# 2021-02-18_HALO_Accel_Board.net
KiCad netlist of a schematic drawn in EAGLE
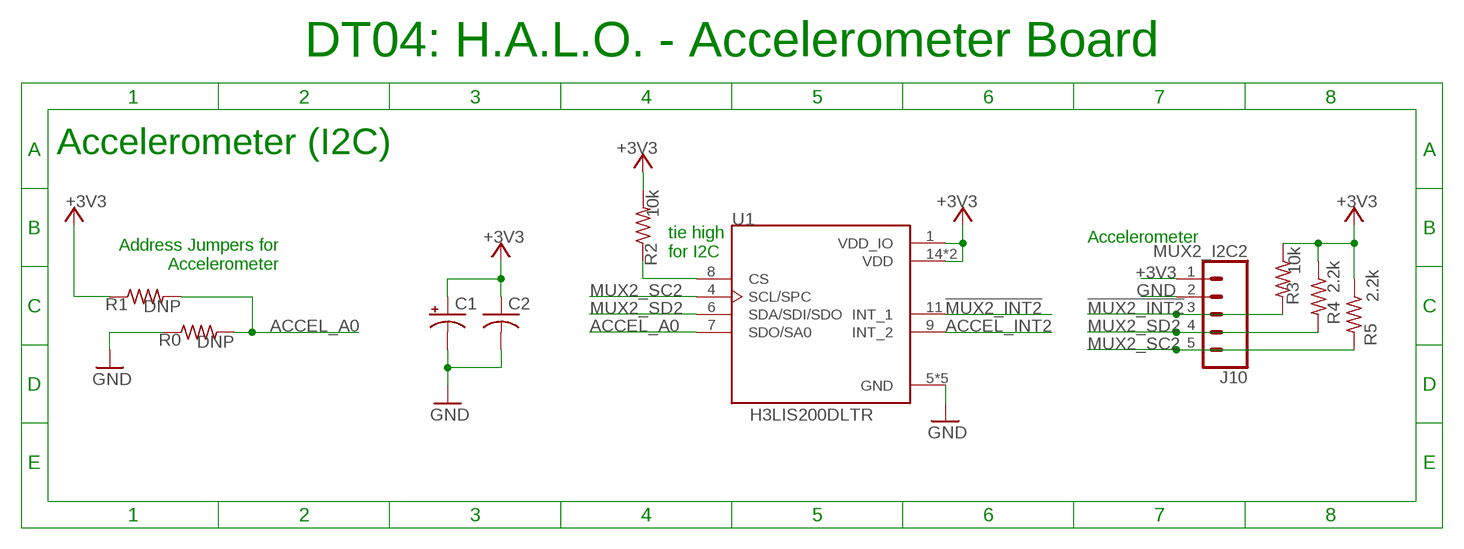
[diagram p0: schematic, sheet 1]

(export (version "E")
  (design (tool "Eeschema 10.0.6"))
  (components
    (comp (ref "C1")
      (value "10uF")
      (footprint "eagle-import:EIA3216")
      (libsource (lib "eagle-import") (part "10UF-POLAR-EIA3216-16V-10%(TANT)"))
    )
    (comp (ref "C2")
      (value "0.1uF")
      (footprint "eagle-import:C0805")
      (libsource (lib "eagle-import") (part "C-USC0805"))
    )
    (comp (ref "J10")
      (value "MUX2_I2C2")
      (footprint "eagle-import:1X05")
      (libsource (lib "eagle-import") (part "CONN_05"))
    )
    (comp (ref "R0")
      (value "DNP")
      (footprint "eagle-import:R0805")
      (libsource (lib "eagle-import") (part "R-US_R0805"))
    )
    (comp (ref "R1")
      (value "DNP")
      (footprint "eagle-import:R0805")
      (libsource (lib "eagle-import") (part "R-US_R0805"))
    )
    (comp (ref "R2")
      (value "10k")
      (footprint "eagle-import:R0805")
      (libsource (lib "eagle-import") (part "R-US_R0805"))
    )
    (comp (ref "R3")
      (value "10k")
      (footprint "eagle-import:R0805")
      (libsource (lib "eagle-import") (part "R-US_R0805"))
    )
    (comp (ref "R4")
      (value "2.2k")
      (footprint "eagle-import:R0805")
      (libsource (lib "eagle-import") (part "R-US_R0805"))
    )
    (comp (ref "R5")
      (value "2.2k")
      (footprint "eagle-import:R0805")
      (libsource (lib "eagle-import") (part "R-US_R0805"))
    )
    (comp (ref "U1")
      (value "H3LIS200DLTR")
      (footprint "eagle-import:PQFN50P300X300X100-16N")
      (fields (field (name "DIGI-KEY_PART_NUMBER") "497-15698-1-ND") (field (name "MF") "STMicroelectronics"))
      (libsource (lib "eagle-import") (part "H3LIS200DLTR"))
    )
  )
  (nets
    (net (code "1") (name "+3V3") (class "Default")
      (node (ref "C1") (pin "+") (pinfunction "+_+") (pintype "passive"))
      (node (ref "C2") (pin "1") (pinfunction "1_1") (pintype "passive"))
      (node (ref "J10") (pin "1") (pinfunction "1_1") (pintype "passive"))
      (node (ref "R1") (pin "1") (pinfunction "1_1") (pintype "passive"))
      (node (ref "R2") (pin "2") (pinfunction "2_2") (pintype "passive"))
      (node (ref "R3") (pin "1") (pinfunction "1_1") (pintype "passive"))
      (node (ref "R4") (pin "1") (pinfunction "1_1") (pintype "passive"))
      (node (ref "R5") (pin "1") (pinfunction "1_1") (pintype "passive"))
      (node (ref "U1") (pin "1") (pinfunction "VDD_IO_1") (pintype "power_in"))
      (node (ref "U1") (pin "14") (pinfunction "VDD_14") (pintype "power_in"))
      (node (ref "U1") (pin "15") (pinfunction "VDD_15") (pintype "power_in"))
    )
    (net (code "2") (name "/ACCEL_A0") (class "Default")
      (node (ref "R0") (pin "2") (pinfunction "2_2") (pintype "passive"))
      (node (ref "R1") (pin "2") (pinfunction "2_2") (pintype "passive"))
      (node (ref "U1") (pin "7") (pinfunction "SDO/SA0_7") (pintype "output"))
    )
    (net (code "3") (name "/ACCEL_INT2") (class "Default")
      (node (ref "U1") (pin "9") (pinfunction "INT_2_9") (pintype "output"))
    )
    (net (code "4") (name "/MUX2_SC2") (class "Default")
      (node (ref "J10") (pin "5") (pinfunction "5_5") (pintype "passive"))
      (node (ref "R5") (pin "2") (pinfunction "2_2") (pintype "passive"))
      (node (ref "U1") (pin "4") (pinfunction "SCL/SPC_4") (pintype "input"))
    )
    (net (code "5") (name "/MUX2_SD2") (class "Default")
      (node (ref "J10") (pin "4") (pinfunction "4_4") (pintype "passive"))
      (node (ref "R4") (pin "2") (pinfunction "2_2") (pintype "passive"))
      (node (ref "U1") (pin "6") (pinfunction "SDA/SDI/SDO_6") (pintype "bidirectional"))
    )
    (net (code "6") (name "/~{MUX2_INT2}") (class "Default")
      (node (ref "J10") (pin "3") (pinfunction "3_3") (pintype "passive"))
      (node (ref "R3") (pin "2") (pinfunction "2_2") (pintype "passive"))
      (node (ref "U1") (pin "11") (pinfunction "INT_1_11") (pintype "output"))
    )
    (net (code "7") (name "GND") (class "Default")
      (node (ref "C1") (pin "-") (pinfunction "-_-") (pintype "passive"))
      (node (ref "C2") (pin "2") (pinfunction "2_2") (pintype "passive"))
      (node (ref "J10") (pin "2") (pinfunction "2_2") (pintype "passive"))
      (node (ref "R0") (pin "1") (pinfunction "1_1") (pintype "passive"))
      (node (ref "U1") (pin "10") (pinfunction "GND_10") (pintype "power_in"))
      (node (ref "U1") (pin "12") (pinfunction "GND_12") (pintype "power_in"))
      (node (ref "U1") (pin "13") (pinfunction "GND_13") (pintype "power_in"))
      (node (ref "U1") (pin "16") (pinfunction "GND_16") (pintype "power_in"))
      (node (ref "U1") (pin "5") (pinfunction "GND_5") (pintype "power_in"))
    )
    (net (code "8") (name "Net-(U1-CS)") (class "Default")
      (node (ref "R2") (pin "1") (pinfunction "1_1") (pintype "passive"))
      (node (ref "U1") (pin "8") (pinfunction "CS_8") (pintype "input"))
    )
  )
)
